# PERfECT-BLE.net
KiCad netlist of a schematic drawn in Altium Designer
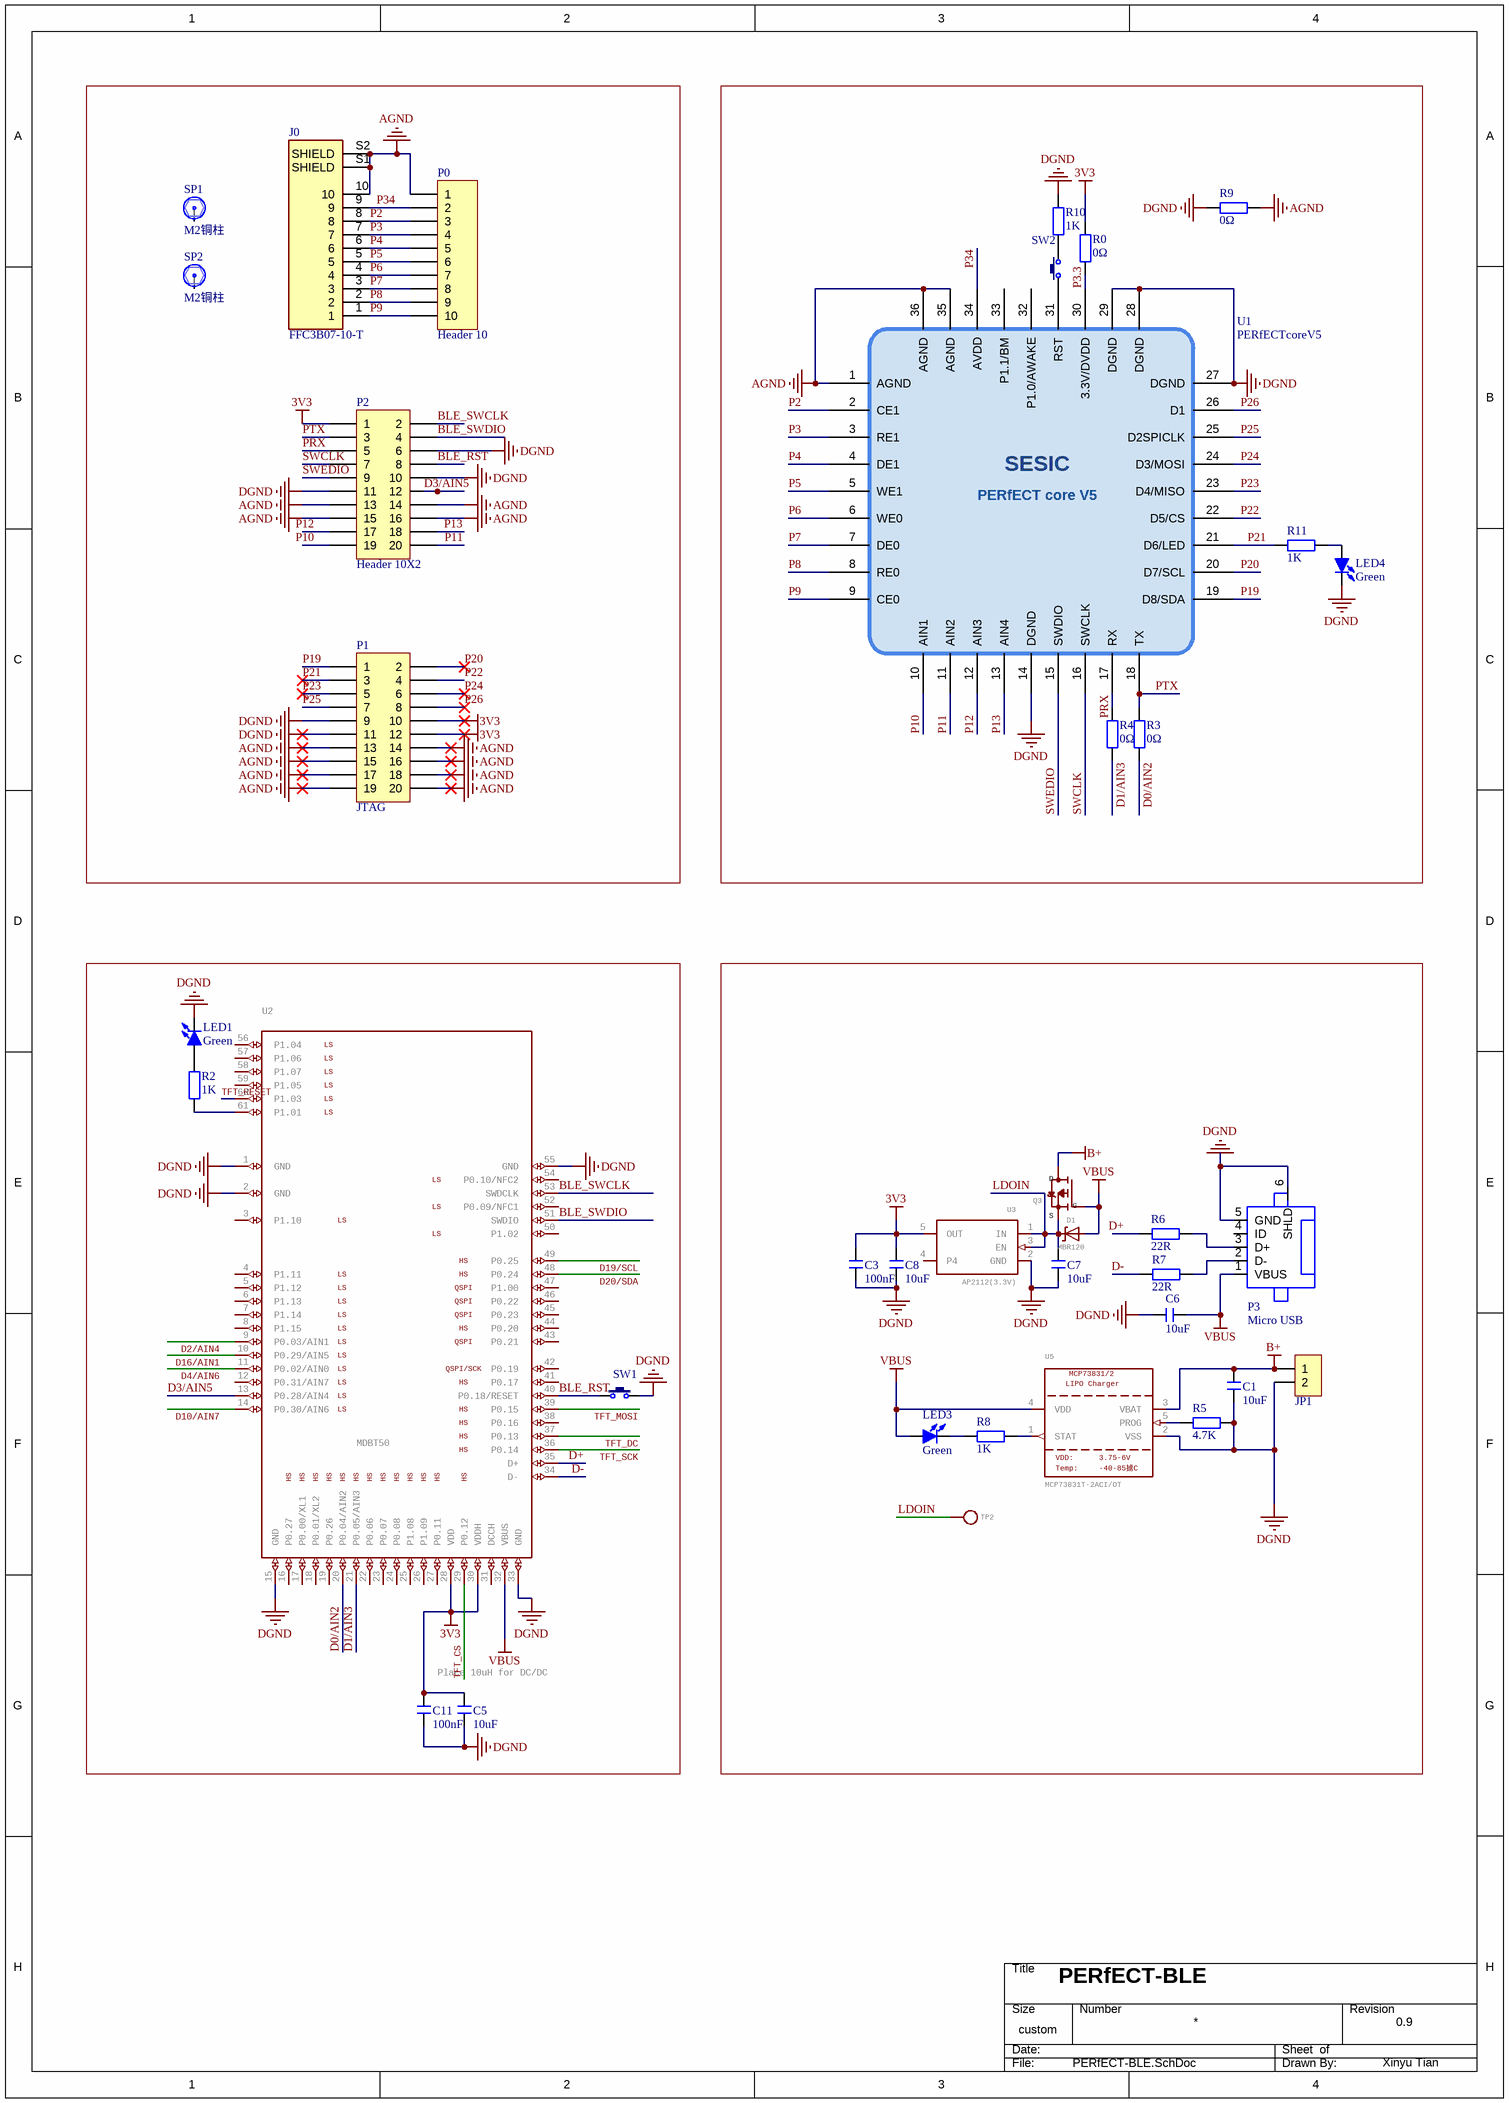
[diagram p0: PERfECT-BLE.SchDoc]

(export (version "E")
  (design (tool "Eeschema 10.0.6"))
  (components
    (comp (ref "C1")
      (value "10uF")
      (footprint "LC-0603_C")
      (description "无极性贴片电容")
      (fields (field (name "版权归属") "源创客"))
      (libsource (lib "3.1   - 电阻-电容-电感") (part "C"))
    )
    (comp (ref "C3")
      (value "100nF")
      (footprint "LC-0603_C")
      (description "无极性贴片电容")
      (fields (field (name "版权归属") "源创客"))
      (libsource (lib "3.1   - 电阻-电容-电感") (part "C"))
    )
    (comp (ref "C5")
      (value "10uF")
      (footprint "LC-0603_C")
      (description "无极性贴片电容")
      (fields (field (name "版权归属") "源创客"))
      (libsource (lib "3.1   - 电阻-电容-电感") (part "C"))
    )
    (comp (ref "C6")
      (value "10uF")
      (footprint "LC-0603_C")
      (description "无极性贴片电容")
      (fields (field (name "版权归属") "源创客"))
      (libsource (lib "3.1   - 电阻-电容-电感") (part "C"))
    )
    (comp (ref "C7")
      (value "10uF")
      (footprint "LC-0603_C")
      (description "无极性贴片电容")
      (fields (field (name "版权归属") "源创客"))
      (libsource (lib "3.1   - 电阻-电容-电感") (part "C"))
    )
    (comp (ref "C8")
      (value "10uF")
      (footprint "LC-0603_C")
      (description "无极性贴片电容")
      (fields (field (name "版权归属") "源创客"))
      (libsource (lib "3.1   - 电阻-电容-电感") (part "C"))
    )
    (comp (ref "C11")
      (value "100nF")
      (footprint "LC-0603_C")
      (description "无极性贴片电容")
      (fields (field (name "版权归属") "源创客"))
      (libsource (lib "3.1   - 电阻-电容-电感") (part "C"))
    )
    (comp (ref "D1")
      (value "MBR120")
      (footprint "LC-SOD-123")
      (libsource (lib "microbuilder") (part "DIODE-SCHOTTKYSOD-123"))
    )
    (comp (ref "J0")
      (value "FFC3B07-10-T")
      (footprint "GCT_FFC3B07-10-T")
      (description "10 Position FFC, FPC Connector Contacts, Bottom 0.039 (1.00mm) Surface Mount, Right Angle")
      (fields (field (name "MF") "Global Connector Technology"))
      (libsource (lib "FFC3B07-10-T") (part "FFC3B07-10-T"))
    )
    (comp (ref "JP1")
      (value "HDR-1X2")
      (footprint "XH2.54-LI-2P")
      (description "2P接插件")
      (fields (field (name "版权归属") "源创客"))
      (libsource (lib "4.5   - 接插件-脚距2.54") (part "Header 2"))
    )
    (comp (ref "LED1")
      (value "Green")
      (footprint "LC-0603_LED_S1")
      (description "贴片LED")
      (fields (field (name "版权归属") "源创客"))
      (libsource (lib "9.1   - LED") (part "LED-SMD"))
    )
    (comp (ref "LED3")
      (value "Green")
      (footprint "0603_LED_S1")
      (description "贴片LED")
      (fields (field (name "版权归属") "源创客"))
      (libsource (lib "9.1   - LED") (part "LED-SMD"))
    )
    (comp (ref "LED4")
      (value "Green")
      (footprint "LC-0603_LED_S1")
      (description "贴片LED")
      (fields (field (name "版权归属") "源创客"))
      (libsource (lib "9.1   - LED") (part "LED-SMD"))
    )
    (comp (ref "P0")
      (value "Header 10")
      (footprint "HDR1X10")
      (description "Header, 10-Pin")
      (fields (field (name "PUBLISHER") "Altium Limited"))
      (libsource (lib "Miscellaneous Connectors") (part "Header 10"))
    )
    (comp (ref "P1")
      (value "JTAG")
      (footprint "HDR2X10")
      (description "Header, 10-Pin, Dual row")
      (fields (field (name "PUBLISHER") "Altium Limited"))
      (libsource (lib "PERfECT-PRO") (part "Header 10X2"))
    )
    (comp (ref "P2")
      (value "Header 10X2")
      (footprint "HDR2X10")
      (description "Header, 10-Pin, Dual row")
      (fields (field (name "PUBLISHER") "Altium Limited"))
      (libsource (lib "PERfECT-PRO") (part "Header 10X2"))
    )
    (comp (ref "P3")
      (value "Micro USB")
      (footprint "1981584-1")
      (description "CONN RCPT MICRO USB TYPE AB")
      (fields (field (name "MANUFACTURER") "REG CON") (field (name "PARTNUMBER") "C21377"))
      (libsource (lib "ESP32D") (part "1981584-1"))
    )
    (comp (ref "Q3")
      (value "DMG2305")
      (footprint "LC-SOT-23-3L")
      (fields (field (name "D") "D") (field (name "S") "S") (field (name "G") "G"))
      (libsource (lib "microbuilder") (part "MOSFET-P"))
    )
    (comp (ref "R0")
      (value "0Ω")
      (footprint "LC-0603_R")
      (description "贴片电阻")
      (fields (field (name "版权归属") "源创客"))
      (libsource (lib "3.1   - 电阻-电容-电感") (part "R"))
    )
    (comp (ref "R2")
      (value "1K")
      (footprint "LC-0603_R")
      (description "贴片电阻")
      (fields (field (name "版权归属") "源创客"))
      (libsource (lib "3.1   - 电阻-电容-电感") (part "R"))
    )
    (comp (ref "R3")
      (value "0Ω")
      (footprint "0603_R")
      (description "贴片电阻")
      (fields (field (name "版权归属") "源创客"))
      (libsource (lib "3.1   - 电阻-电容-电感") (part "R"))
    )
    (comp (ref "R4")
      (value "0Ω")
      (footprint "0603_R")
      (description "贴片电阻")
      (fields (field (name "版权归属") "源创客"))
      (libsource (lib "3.1   - 电阻-电容-电感") (part "R"))
    )
    (comp (ref "R5")
      (value "4.7K")
      (footprint "LC-0603_R")
      (description "贴片电阻")
      (fields (field (name "版权归属") "源创客"))
      (libsource (lib "3.1   - 电阻-电容-电感") (part "R"))
    )
    (comp (ref "R6")
      (value "22R")
      (footprint "LC-0603_R")
      (description "贴片电阻")
      (fields (field (name "版权归属") "源创客"))
      (libsource (lib "3.1   - 电阻-电容-电感") (part "R"))
    )
    (comp (ref "R7")
      (value "22R")
      (footprint "LC-0603_R")
      (description "贴片电阻")
      (fields (field (name "版权归属") "源创客"))
      (libsource (lib "3.1   - 电阻-电容-电感") (part "R"))
    )
    (comp (ref "R8")
      (value "1K")
      (footprint "0603_R")
      (description "贴片电阻")
      (fields (field (name "版权归属") "源创客"))
      (libsource (lib "3.1   - 电阻-电容-电感") (part "R"))
    )
    (comp (ref "R9")
      (value "0Ω")
      (footprint "LC-0603_R")
      (description "贴片电阻")
      (fields (field (name "版权归属") "源创客"))
      (libsource (lib "3.1   - 电阻-电容-电感") (part "R"))
    )
    (comp (ref "R10")
      (value "1K")
      (footprint "LC-0603_R")
      (description "贴片电阻")
      (fields (field (name "版权归属") "源创客"))
      (libsource (lib "3.1   - 电阻-电容-电感") (part "R"))
    )
    (comp (ref "R11")
      (value "1K")
      (footprint "LC-0603_R")
      (description "贴片电阻")
      (fields (field (name "版权归属") "源创客"))
      (libsource (lib "3.1   - 电阻-电容-电感") (part "R"))
    )
    (comp (ref "SP1")
      (value "M2铜柱")
      (footprint "M3x4_L")
      (description "铜柱")
      (fields (field (name "版权归属") "源创客"))
      (libsource (lib "15.1 - 未分类器件") (part "铜柱小焊盘"))
    )
    (comp (ref "SP2")
      (value "M2铜柱")
      (footprint "M3x4_L")
      (description "铜柱")
      (fields (field (name "版权归属") "源创客"))
      (libsource (lib "15.1 - 未分类器件") (part "铜柱小焊盘"))
    )
    (comp (ref "SW1")
      (value "3x6x5")
      (footprint "TSW SMD-3*6*2.5")
      (description "3x6轻触开关")
      (fields (field (name "版权归属") "源创客"))
      (libsource (lib "") (part "TSW 3x6_1"))
    )
    (comp (ref "SW2")
      (value "3x6x5")
      (footprint "TSW SMD-3*6*2.5")
      (description "3x6轻触开关")
      (fields (field (name "版权归属") "源创客"))
      (libsource (lib "5.1   - 按键-开关") (part "TSW 3x6"))
    )
    (comp (ref "TP2")
      (value "TESTPOINTROUND1.5MM")
      (footprint "TESTPOINT_ROUND_1.5MM")
      (libsource (lib "microbuilder") (part "TESTPOINTROUND1.5MM"))
    )
    (comp (ref "U1")
      (value "PERfECTcoreV5")
      (footprint "PERfECTcore36")
      (description "This is the 5th version of PERfEC core.https://github.com/WISE-PERfECT/PERfECT")
      (libsource (lib "PERfECT-PRO") (part "PERfECTcoreV5"))
    )
    (comp (ref "U2")
      (value "MDBT50")
      (footprint "MDBT50")
      (fields
        (field (name "LS") "LS")
        (field (name "LS_1") "LS")
        (field (name "LS_2") "LS")
        (field (name "LS_3") "LS")
        (field (name "LS_4") "LS")
        (field (name "LS_5") "LS")
        (field (name "LS_6") "LS")
        (field (name "LS_7") "LS")
        (field (name "LS_8") "LS")
        (field (name "HS") "HS")
        (field (name "HS_1") "HS")
        (field (name "HS_2") "HS")
        (field (name "HS_3") "HS")
        (field (name "HS_4") "HS")
        (field (name "HS_5") "HS")
        (field (name "HS_6") "HS")
        (field (name "HS_7") "HS")
        (field (name "HS_8") "HS")
        (field (name "QSPI") "QSPI")
        (field (name "QSPI_1") "QSPI")
        (field (name "QSPI_2") "QSPI")
        (field (name "QSPI_3") "QSPI")
        (field (name "QSPI/SCK") "QSPI/SCK")
      )
      (libsource (lib "microbuilder") (part "MDBT50"))
    )
    (comp (ref "U3")
      (value "AP2112(3.3V)")
      (footprint "Probe-Scope v1.0:SOT23-5")
      (libsource (lib "microbuilder") (part "VREG_SOT23-5"))
    )
    (comp (ref "U5")
      (value "MCP73831T-2ACI/OT")
      (footprint "SOT23-5")
      (fields
        (field (name "MCP73831/2") "MCP73831/2")
        (field (name "LIPOCHARGER") "LIPO Charger")
        (field (name "TEMP") "Temp:")
        (field (name "-40-85掳C") "-40-85掳C")
        (field (name "VDD") "VDD:")
        (field (name "3.75-6V") "3.75-6V")
      )
      (libsource (lib "microbuilder") (part "MCP73831/2"))
    )
  )
  (nets
    (net (code "1") (name "/BLE_RST") (class "Default")
      (node (ref "P2") (pin "8") (pinfunction "8_8") (pintype "passive"))
      (node (ref "SW1") (pin "1") (pinfunction "1_1") (pintype "passive"))
      (node (ref "U2") (pin "40") (pinfunction "P0.18/RESET_40") (pintype "bidirectional"))
    )
    (net (code "2") (name "/BLE_SWCLK") (class "Default")
      (node (ref "P2") (pin "2") (pinfunction "2_2") (pintype "passive"))
      (node (ref "U2") (pin "53") (pinfunction "SWDCLK_53") (pintype "bidirectional"))
    )
    (net (code "3") (name "/BLE_SWDIO") (class "Default")
      (node (ref "P2") (pin "4") (pinfunction "4_4") (pintype "passive"))
      (node (ref "U2") (pin "51") (pinfunction "SWDIO_51") (pintype "bidirectional"))
    )
    (net (code "4") (name "/D+") (class "Default")
      (node (ref "R6") (pin "1") (pinfunction "1_1") (pintype "passive"))
      (node (ref "U2") (pin "35") (pinfunction "D+_35") (pintype "bidirectional"))
    )
    (net (code "5") (name "/D-") (class "Default")
      (node (ref "R7") (pin "1") (pinfunction "1_1") (pintype "passive"))
      (node (ref "U2") (pin "34") (pinfunction "D-_34") (pintype "bidirectional"))
    )
    (net (code "6") (name "/D0{slash}AIN2") (class "Default")
      (node (ref "R3") (pin "2") (pinfunction "2_2") (pintype "passive"))
      (node (ref "U2") (pin "20") (pinfunction "P0.04/AIN2_20") (pintype "bidirectional"))
    )
    (net (code "7") (name "/D1{slash}AIN3") (class "Default")
      (node (ref "R4") (pin "2") (pinfunction "2_2") (pintype "passive"))
      (node (ref "U2") (pin "21") (pinfunction "P0.05/AIN3_21") (pintype "bidirectional"))
    )
    (net (code "8") (name "/D2{slash}AIN4") (class "Default")
      (node (ref "U2") (pin "9") (pinfunction "P0.03/AIN1_9") (pintype "bidirectional"))
    )
    (net (code "9") (name "/D3{slash}AIN5") (class "Default")
      (node (ref "P2") (pin "12") (pinfunction "12_12") (pintype "passive"))
      (node (ref "U2") (pin "13") (pinfunction "P0.28/AIN4_13") (pintype "bidirectional"))
    )
    (net (code "10") (name "/D4{slash}AIN6") (class "Default")
      (node (ref "U2") (pin "11") (pinfunction "P0.02/AIN0_11") (pintype "bidirectional"))
    )
    (net (code "11") (name "/D10{slash}AIN7") (class "Default")
      (node (ref "U2") (pin "14") (pinfunction "P0.30/AIN6_14") (pintype "bidirectional"))
    )
    (net (code "12") (name "/D16{slash}AIN1") (class "Default")
      (node (ref "U2") (pin "10") (pinfunction "P0.29/AIN5_10") (pintype "bidirectional"))
    )
    (net (code "13") (name "/D19{slash}SCL") (class "Default")
      (node (ref "U2") (pin "49") (pinfunction "P0.25_49") (pintype "bidirectional"))
    )
    (net (code "14") (name "/D20{slash}SDA") (class "Default")
      (node (ref "U2") (pin "48") (pinfunction "P0.24_48") (pintype "bidirectional"))
    )
    (net (code "15") (name "/LDOIN") (class "Default")
      (node (ref "C7") (pin "2") (pinfunction "2_2") (pintype "passive"))
      (node (ref "D1") (pin "C") (pinfunction "C_C") (pintype "passive"))
      (node (ref "Q3") (pin "2") (pinfunction "S_2") (pintype "passive"))
      (node (ref "TP2") (pin "P$1") (pinfunction "P$1_P$1") (pintype "bidirectional"))
      (node (ref "U3") (pin "1") (pinfunction "IN_1") (pintype "power_in"))
      (node (ref "U3") (pin "3") (pinfunction "EN_3") (pintype "input"))
    )
    (net (code "16") (name "/P2") (class "Default")
      (node (ref "J0") (pin "8") (pinfunction "8_8") (pintype "passive"))
      (node (ref "P0") (pin "3") (pinfunction "3_3") (pintype "passive"))
      (node (ref "U1") (pin "2") (pinfunction "CE1_2") (pintype "passive"))
    )
    (net (code "17") (name "/P3") (class "Default")
      (node (ref "J0") (pin "7") (pinfunction "7_7") (pintype "passive"))
      (node (ref "P0") (pin "4") (pinfunction "4_4") (pintype "passive"))
      (node (ref "U1") (pin "3") (pinfunction "RE1_3") (pintype "passive"))
    )
    (net (code "18") (name "/P3.3") (class "Default")
      (node (ref "R0") (pin "2") (pinfunction "2_2") (pintype "passive"))
      (node (ref "U1") (pin "30") (pinfunction "3.3V/DVDD_30") (pintype "passive"))
    )
    (net (code "19") (name "/P4") (class "Default")
      (node (ref "J0") (pin "6") (pinfunction "6_6") (pintype "passive"))
      (node (ref "P0") (pin "5") (pinfunction "5_5") (pintype "passive"))
      (node (ref "U1") (pin "4") (pinfunction "DE1_4") (pintype "passive"))
    )
    (net (code "20") (name "/P5") (class "Default")
      (node (ref "J0") (pin "5") (pinfunction "5_5") (pintype "passive"))
      (node (ref "P0") (pin "6") (pinfunction "6_6") (pintype "passive"))
      (node (ref "U1") (pin "5") (pinfunction "WE1_5") (pintype "passive"))
    )
    (net (code "21") (name "/P6") (class "Default")
      (node (ref "J0") (pin "4") (pinfunction "4_4") (pintype "passive"))
      (node (ref "P0") (pin "7") (pinfunction "7_7") (pintype "passive"))
      (node (ref "U1") (pin "6") (pinfunction "WE0_6") (pintype "passive"))
    )
    (net (code "22") (name "/P7") (class "Default")
      (node (ref "J0") (pin "3") (pinfunction "3_3") (pintype "passive"))
      (node (ref "P0") (pin "8") (pinfunction "8_8") (pintype "passive"))
      (node (ref "U1") (pin "7") (pinfunction "DE0_7") (pintype "passive"))
    )
    (net (code "23") (name "/P8") (class "Default")
      (node (ref "J0") (pin "2") (pinfunction "2_2") (pintype "passive"))
      (node (ref "P0") (pin "9") (pinfunction "9_9") (pintype "passive"))
      (node (ref "U1") (pin "8") (pinfunction "RE0_8") (pintype "passive"))
    )
    (net (code "24") (name "/P9") (class "Default")
      (node (ref "J0") (pin "1") (pinfunction "1_1") (pintype "passive"))
      (node (ref "P0") (pin "10") (pinfunction "10_10") (pintype "passive"))
      (node (ref "U1") (pin "9") (pinfunction "CE0_9") (pintype "passive"))
    )
    (net (code "25") (name "/P10") (class "Default")
      (node (ref "P2") (pin "19") (pinfunction "19_19") (pintype "passive"))
      (node (ref "U1") (pin "10") (pinfunction "AIN1_10") (pintype "passive"))
    )
    (net (code "26") (name "/P11") (class "Default")
      (node (ref "P2") (pin "20") (pinfunction "20_20") (pintype "passive"))
      (node (ref "U1") (pin "11") (pinfunction "AIN2_11") (pintype "passive"))
    )
    (net (code "27") (name "/P12") (class "Default")
      (node (ref "P2") (pin "17") (pinfunction "17_17") (pintype "passive"))
      (node (ref "U1") (pin "12") (pinfunction "AIN3_12") (pintype "passive"))
    )
    (net (code "28") (name "/P13") (class "Default")
      (node (ref "P2") (pin "18") (pinfunction "18_18") (pintype "passive"))
      (node (ref "U1") (pin "13") (pinfunction "AIN4_13") (pintype "passive"))
    )
    (net (code "29") (name "/P19") (class "Default")
      (node (ref "P1") (pin "1") (pinfunction "1_1") (pintype "passive"))
      (node (ref "U1") (pin "19") (pinfunction "D8/SDA_19") (pintype "passive"))
    )
    (net (code "30") (name "/P20") (class "Default")
      (node (ref "P1") (pin "2") (pinfunction "2_2") (pintype "passive"))
      (node (ref "U1") (pin "20") (pinfunction "D7/SCL_20") (pintype "passive"))
    )
    (net (code "31") (name "/P21") (class "Default")
      (node (ref "P1") (pin "3") (pinfunction "3_3") (pintype "passive"))
      (node (ref "R11") (pin "1") (pinfunction "1_1") (pintype "passive"))
      (node (ref "U1") (pin "21") (pinfunction "D6/LED_21") (pintype "passive"))
    )
    (net (code "32") (name "/P22") (class "Default")
      (node (ref "P1") (pin "4") (pinfunction "4_4") (pintype "passive"))
      (node (ref "U1") (pin "22") (pinfunction "D5/CS_22") (pintype "passive"))
    )
    (net (code "33") (name "/P23") (class "Default")
      (node (ref "P1") (pin "5") (pinfunction "5_5") (pintype "passive"))
      (node (ref "U1") (pin "23") (pinfunction "D4/MISO_23") (pintype "passive"))
    )
    (net (code "34") (name "/P24") (class "Default")
      (node (ref "P1") (pin "6") (pinfunction "6_6") (pintype "passive"))
      (node (ref "U1") (pin "24") (pinfunction "D3/MOSI_24") (pintype "passive"))
    )
    (net (code "35") (name "/P25") (class "Default")
      (node (ref "P1") (pin "7") (pinfunction "7_7") (pintype "passive"))
      (node (ref "U1") (pin "25") (pinfunction "D2SPICLK_25") (pintype "passive"))
    )
    (net (code "36") (name "/P26") (class "Default")
      (node (ref "P1") (pin "8") (pinfunction "8_8") (pintype "passive"))
      (node (ref "U1") (pin "26") (pinfunction "D1_26") (pintype "passive"))
    )
    (net (code "37") (name "/P34") (class "Default")
      (node (ref "J0") (pin "9") (pinfunction "9_9") (pintype "passive"))
      (node (ref "P0") (pin "2") (pinfunction "2_2") (pintype "passive"))
      (node (ref "U1") (pin "34") (pinfunction "AVDD_34") (pintype "passive"))
    )
    (net (code "38") (name "/PRX") (class "Default")
      (node (ref "P2") (pin "5") (pinfunction "5_5") (pintype "passive"))
      (node (ref "R4") (pin "1") (pinfunction "1_1") (pintype "passive"))
      (node (ref "U1") (pin "17") (pinfunction "RX_17") (pintype "passive"))
    )
    (net (code "39") (name "/PTX") (class "Default")
      (node (ref "P2") (pin "3") (pinfunction "3_3") (pintype "passive"))
      (node (ref "R3") (pin "1") (pinfunction "1_1") (pintype "passive"))
      (node (ref "U1") (pin "18") (pinfunction "TX_18") (pintype "passive"))
    )
    (net (code "40") (name "/SWCLK") (class "Default")
      (node (ref "P2") (pin "7") (pinfunction "7_7") (pintype "passive"))
      (node (ref "U1") (pin "16") (pinfunction "SWCLK_16") (pintype "passive"))
    )
    (net (code "41") (name "/SWEDIO") (class "Default")
      (node (ref "P2") (pin "9") (pinfunction "9_9") (pintype "passive"))
      (node (ref "U1") (pin "15") (pinfunction "SWDIO_15") (pintype "passive"))
    )
    (net (code "42") (name "/TFT_CS") (class "Default")
      (node (ref "U2") (pin "29") (pinfunction "P0.12_29") (pintype "bidirectional"))
    )
    (net (code "43") (name "/TFT_DC") (class "Default")
      (node (ref "U2") (pin "37") (pinfunction "P0.13_37") (pintype "bidirectional"))
    )
    (net (code "44") (name "/TFT_MOSI") (class "Default")
      (node (ref "U2") (pin "39") (pinfunction "P0.15_39") (pintype "bidirectional"))
    )
    (net (code "45") (name "/TFT_RESET") (class "Default")
      (node (ref "U2") (pin "60") (pinfunction "P1.03_60") (pintype "bidirectional"))
    )
    (net (code "46") (name "/TFT_SCK") (class "Default")
      (node (ref "U2") (pin "36") (pinfunction "P0.14_36") (pintype "bidirectional"))
    )
    (net (code "47") (name "3V3") (class "Default")
      (node (ref "C11") (pin "2") (pinfunction "2_2") (pintype "passive"))
      (node (ref "C3") (pin "2") (pinfunction "2_2") (pintype "passive"))
      (node (ref "C5") (pin "2") (pinfunction "2_2") (pintype "passive"))
      (node (ref "C8") (pin "2") (pinfunction "2_2") (pintype "passive"))
      (node (ref "P1") (pin "10") (pinfunction "10_10") (pintype "passive"))
      (node (ref "P1") (pin "12") (pinfunction "12_12") (pintype "passive"))
      (node (ref "P2") (pin "1") (pinfunction "1_1") (pintype "passive"))
      (node (ref "R0") (pin "1") (pinfunction "1_1") (pintype "passive"))
      (node (ref "U2") (pin "28") (pinfunction "VDD_28") (pintype "bidirectional"))
      (node (ref "U2") (pin "30") (pinfunction "VDDH_30") (pintype "bidirectional"))
      (node (ref "U3") (pin "5") (pinfunction "OUT_5") (pintype "power_in"))
    )
    (net (code "48") (name "AGND") (class "Default")
      (node (ref "J0") (pin "10") (pinfunction "10_10") (pintype "passive"))
      (node (ref "J0") (pin "S1") (pinfunction "SHIELD_S1") (pintype "passive"))
      (node (ref "J0") (pin "S2") (pinfunction "SHIELD_S2") (pintype "passive"))
      (node (ref "P0") (pin "1") (pinfunction "1_1") (pintype "passive"))
      (node (ref "P1") (pin "13") (pinfunction "13_13") (pintype "passive"))
      (node (ref "P1") (pin "14") (pinfunction "14_14") (pintype "passive"))
      (node (ref "P1") (pin "15") (pinfunction "15_15") (pintype "passive"))
      (node (ref "P1") (pin "16") (pinfunction "16_16") (pintype "passive"))
      (node (ref "P1") (pin "17") (pinfunction "17_17") (pintype "passive"))
      (node (ref "P1") (pin "18") (pinfunction "18_18") (pintype "passive"))
      (node (ref "P1") (pin "19") (pinfunction "19_19") (pintype "passive"))
      (node (ref "P1") (pin "20") (pinfunction "20_20") (pintype "passive"))
      (node (ref "P2") (pin "13") (pinfunction "13_13") (pintype "passive"))
      (node (ref "P2") (pin "14") (pinfunction "14_14") (pintype "passive"))
      (node (ref "P2") (pin "15") (pinfunction "15_15") (pintype "passive"))
      (node (ref "P2") (pin "16") (pinfunction "16_16") (pintype "passive"))
      (node (ref "R9") (pin "2") (pinfunction "2_2") (pintype "passive"))
      (node (ref "U1") (pin "1") (pinfunction "AGND_1") (pintype "passive"))
      (node (ref "U1") (pin "35") (pinfunction "AGND_35") (pintype "passive"))
      (node (ref "U1") (pin "36") (pinfunction "AGND_36") (pintype "passive"))
    )
    (net (code "49") (name "B+") (class "Default")
      (node (ref "C1") (pin "2") (pinfunction "2_2") (pintype "passive"))
      (node (ref "JP1") (pin "1") (pinfunction "1_1") (pintype "passive"))
      (node (ref "Q3") (pin "3") (pinfunction "D_3") (pintype "passive"))
      (node (ref "U5") (pin "3") (pinfunction "VBAT_3") (pintype "power_in"))
    )
    (net (code "50") (name "DGND") (class "Default")
      (node (ref "C1") (pin "1") (pinfunction "1_1") (pintype "passive"))
      (node (ref "C11") (pin "1") (pinfunction "1_1") (pintype "passive"))
      (node (ref "C3") (pin "1") (pinfunction "1_1") (pintype "passive"))
      (node (ref "C5") (pin "1") (pinfunction "1_1") (pintype "passive"))
      (node (ref "C6") (pin "2") (pinfunction "2_2") (pintype "passive"))
      (node (ref "C7") (pin "1") (pinfunction "1_1") (pintype "passive"))
      (node (ref "C8") (pin "1") (pinfunction "1_1") (pintype "passive"))
      (node (ref "JP1") (pin "2") (pinfunction "2_2") (pintype "passive"))
      (node (ref "LED1") (pin "2") (pinfunction "K_2") (pintype "passive"))
      (node (ref "LED4") (pin "2") (pinfunction "K_2") (pintype "passive"))
      (node (ref "P1") (pin "11") (pinfunction "11_11") (pintype "passive"))
      (node (ref "P1") (pin "9") (pinfunction "9_9") (pintype "passive"))
      (node (ref "P2") (pin "10") (pinfunction "10_10") (pintype "passive"))
      (node (ref "P2") (pin "11") (pinfunction "11_11") (pintype "passive"))
      (node (ref "P2") (pin "6") (pinfunction "6_6") (pintype "passive"))
      (node (ref "P3") (pin "5") (pinfunction "GND_5") (pintype "power_in"))
      (node (ref "P3") (pin "6") (pinfunction "SHLD_6") (pintype "power_in"))
      (node (ref "R10") (pin "2") (pinfunction "2_2") (pintype "passive"))
      (node (ref "R5") (pin "2") (pinfunction "2_2") (pintype "passive"))
      (node (ref "R9") (pin "1") (pinfunction "1_1") (pintype "passive"))
      (node (ref "SW1") (pin "2") (pinfunction "2_2") (pintype "passive"))
      (node (ref "U1") (pin "14") (pinfunction "DGND_14") (pintype "passive"))
      (node (ref "U1") (pin "27") (pinfunction "DGND_27") (pintype "passive"))
      (node (ref "U1") (pin "28") (pinfunction "DGND_28") (pintype "power_in"))
      (node (ref "U1") (pin "29") (pinfunction "DGND_29") (pintype "passive"))
      (node (ref "U2") (pin "1") (pinfunction "GND_1") (pintype "bidirectional"))
      (node (ref "U2") (pin "15") (pinfunction "GND_15") (pintype "bidirectional"))
      (node (ref "U2") (pin "2") (pinfunction "GND_2") (pintype "bidirectional"))
      (node (ref "U2") (pin "33") (pinfunction "GND_33") (pintype "bidirectional"))
      (node (ref "U2") (pin "55") (pinfunction "GND_55") (pintype "bidirectional"))
      (node (ref "U3") (pin "2") (pinfunction "GND_2") (pintype "power_in"))
      (node (ref "U5") (pin "2") (pinfunction "VSS_2") (pintype "power_in"))
    )
    (net (code "51") (name "Net-(LED1-A)") (class "Default")
      (node (ref "LED1") (pin "1") (pinfunction "A_1") (pintype "passive"))
      (node (ref "R2") (pin "2") (pinfunction "2_2") (pintype "passive"))
    )
    (net (code "52") (name "Net-(LED3-K)") (class "Default")
      (node (ref "LED3") (pin "2") (pinfunction "K_2") (pintype "passive"))
      (node (ref "R8") (pin "1") (pinfunction "1_1") (pintype "passive"))
    )
    (net (code "53") (name "Net-(LED4-A)") (class "Default")
      (node (ref "LED4") (pin "1") (pinfunction "A_1") (pintype "passive"))
      (node (ref "R11") (pin "2") (pinfunction "2_2") (pintype "passive"))
    )
    (net (code "54") (name "Net-(P3-D+)") (class "Default")
      (node (ref "P3") (pin "3") (pinfunction "D+_3") (pintype "passive"))
      (node (ref "R6") (pin "2") (pinfunction "2_2") (pintype "passive"))
    )
    (net (code "55") (name "Net-(P3-D-)") (class "Default")
      (node (ref "P3") (pin "2") (pinfunction "D-_2") (pintype "passive"))
      (node (ref "R7") (pin "2") (pinfunction "2_2") (pintype "passive"))
    )
    (net (code "56") (name "Net-(R10-Pad1)") (class "Default")
      (node (ref "R10") (pin "1") (pinfunction "1_1") (pintype "passive"))
      (node (ref "SW2") (pin "2") (pinfunction "2_2") (pintype "passive"))
    )
    (net (code "57") (name "Net-(U1-RST)") (class "Default")
      (node (ref "SW2") (pin "1") (pinfunction "1_1") (pintype "passive"))
      (node (ref "U1") (pin "31") (pinfunction "RST_31") (pintype "passive"))
    )
    (net (code "58") (name "Net-(U2-P1.01)") (class "Default")
      (node (ref "R2") (pin "1") (pinfunction "1_1") (pintype "passive"))
      (node (ref "U2") (pin "61") (pinfunction "P1.01_61") (pintype "bidirectional"))
    )
    (net (code "59") (name "Net-(U5-PROG)") (class "Default")
      (node (ref "R5") (pin "1") (pinfunction "1_1") (pintype "passive"))
      (node (ref "U5") (pin "5") (pinfunction "PROG_5") (pintype "input"))
    )
    (net (code "60") (name "Net-(U5-STAT)") (class "Default")
      (node (ref "R8") (pin "2") (pinfunction "2_2") (pintype "passive"))
      (node (ref "U5") (pin "1") (pinfunction "STAT_1") (pintype "output"))
    )
    (net (code "61") (name "VBUS") (class "Default")
      (node (ref "C6") (pin "1") (pinfunction "1_1") (pintype "passive"))
      (node (ref "D1") (pin "A") (pinfunction "A_A") (pintype "passive"))
      (node (ref "LED3") (pin "1") (pinfunction "A_1") (pintype "passive"))
      (node (ref "P3") (pin "1") (pinfunction "VBUS_1") (pintype "power_in"))
      (node (ref "Q3") (pin "1") (pinfunction "G_1") (pintype "passive"))
      (node (ref "U2") (pin "32") (pinfunction "VBUS_32") (pintype "bidirectional"))
      (node (ref "U5") (pin "4") (pinfunction "VDD_4") (pintype "power_in"))
    )
    (net (code "62") (name "unconnected-(P3-ID-Pad4)") (class "Default")
      (node (ref "P3") (pin "4") (pinfunction "ID_4") (pintype "passive"))
    )
    (net (code "63") (name "unconnected-(SP1-Pad1)") (class "Default")
      (node (ref "SP1") (pin "1") (pinfunction "1_1") (pintype "passive"))
    )
    (net (code "64") (name "unconnected-(SP2-Pad1)") (class "Default")
      (node (ref "SP2") (pin "1") (pinfunction "1_1") (pintype "passive"))
    )
    (net (code "65") (name "unconnected-(U1-P1.0{slash}AWAKE-Pad32)") (class "Default")
      (node (ref "U1") (pin "32") (pinfunction "P1.0/AWAKE_32") (pintype "passive"))
    )
    (net (code "66") (name "unconnected-(U1-P1.1{slash}BM-Pad33)") (class "Default")
      (node (ref "U1") (pin "33") (pinfunction "P1.1/BM_33") (pintype "passive"))
    )
    (net (code "67") (name "unconnected-(U2-DCCH-Pad31)") (class "Default")
      (node (ref "U2") (pin "31") (pinfunction "DCCH_31") (pintype "bidirectional"))
    )
    (net (code "68") (name "unconnected-(U2-P0.00{slash}XL1-Pad17)") (class "Default")
      (node (ref "U2") (pin "17") (pinfunction "P0.00/XL1_17") (pintype "bidirectional"))
    )
    (net (code "69") (name "unconnected-(U2-P0.01{slash}XL2-Pad18)") (class "Default")
      (node (ref "U2") (pin "18") (pinfunction "P0.01/XL2_18") (pintype "bidirectional"))
    )
    (net (code "70") (name "unconnected-(U2-P0.06-Pad22)") (class "Default")
      (node (ref "U2") (pin "22") (pinfunction "P0.06_22") (pintype "bidirectional"))
    )
    (net (code "71") (name "unconnected-(U2-P0.07-Pad23)") (class "Default")
      (node (ref "U2") (pin "23") (pinfunction "P0.07_23") (pintype "bidirectional"))
    )
    (net (code "72") (name "unconnected-(U2-P0.08-Pad24)") (class "Default")
      (node (ref "U2") (pin "24") (pinfunction "P0.08_24") (pintype "bidirectional"))
    )
    (net (code "73") (name "unconnected-(U2-P0.09{slash}NFC1-Pad52)") (class "Default")
      (node (ref "U2") (pin "52") (pinfunction "P0.09/NFC1_52") (pintype "bidirectional"))
    )
    (net (code "74") (name "unconnected-(U2-P0.10{slash}NFC2-Pad54)") (class "Default")
      (node (ref "U2") (pin "54") (pinfunction "P0.10/NFC2_54") (pintype "bidirectional"))
    )
    (net (code "75") (name "unconnected-(U2-P0.11-Pad27)") (class "Default")
      (node (ref "U2") (pin "27") (pinfunction "P0.11_27") (pintype "bidirectional"))
    )
    (net (code "76") (name "unconnected-(U2-P0.16-Pad38)") (class "Default")
      (node (ref "U2") (pin "38") (pinfunction "P0.16_38") (pintype "bidirectional"))
    )
    (net (code "77") (name "unconnected-(U2-P0.17-Pad41)") (class "Default")
      (node (ref "U2") (pin "41") (pinfunction "P0.17_41") (pintype "bidirectional"))
    )
    (net (code "78") (name "unconnected-(U2-P0.19-Pad42)") (class "Default")
      (node (ref "U2") (pin "42") (pinfunction "P0.19_42") (pintype "bidirectional"))
    )
    (net (code "79") (name "unconnected-(U2-P0.20-Pad44)") (class "Default")
      (node (ref "U2") (pin "44") (pinfunction "P0.20_44") (pintype "bidirectional"))
    )
    (net (code "80") (name "unconnected-(U2-P0.21-Pad43)") (class "Default")
      (node (ref "U2") (pin "43") (pinfunction "P0.21_43") (pintype "bidirectional"))
    )
    (net (code "81") (name "unconnected-(U2-P0.22-Pad46)") (class "Default")
      (node (ref "U2") (pin "46") (pinfunction "P0.22_46") (pintype "bidirectional"))
    )
    (net (code "82") (name "unconnected-(U2-P0.23-Pad45)") (class "Default")
      (node (ref "U2") (pin "45") (pinfunction "P0.23_45") (pintype "bidirectional"))
    )
    (net (code "83") (name "unconnected-(U2-P0.26-Pad19)") (class "Default")
      (node (ref "U2") (pin "19") (pinfunction "P0.26_19") (pintype "bidirectional"))
    )
    (net (code "84") (name "unconnected-(U2-P0.27-Pad16)") (class "Default")
      (node (ref "U2") (pin "16") (pinfunction "P0.27_16") (pintype "bidirectional"))
    )
    (net (code "85") (name "unconnected-(U2-P0.31{slash}AIN7-Pad12)") (class "Default")
      (node (ref "U2") (pin "12") (pinfunction "P0.31/AIN7_12") (pintype "bidirectional"))
    )
    (net (code "86") (name "unconnected-(U2-P1.00-Pad47)") (class "Default")
      (node (ref "U2") (pin "47") (pinfunction "P1.00_47") (pintype "bidirectional"))
    )
    (net (code "87") (name "unconnected-(U2-P1.02-Pad50)") (class "Default")
      (node (ref "U2") (pin "50") (pinfunction "P1.02_50") (pintype "bidirectional"))
    )
    (net (code "88") (name "unconnected-(U2-P1.04-Pad56)") (class "Default")
      (node (ref "U2") (pin "56") (pinfunction "P1.04_56") (pintype "bidirectional"))
    )
    (net (code "89") (name "unconnected-(U2-P1.05-Pad59)") (class "Default")
      (node (ref "U2") (pin "59") (pinfunction "P1.05_59") (pintype "bidirectional"))
    )
    (net (code "90") (name "unconnected-(U2-P1.06-Pad57)") (class "Default")
      (node (ref "U2") (pin "57") (pinfunction "P1.06_57") (pintype "bidirectional"))
    )
    (net (code "91") (name "unconnected-(U2-P1.07-Pad58)") (class "Default")
      (node (ref "U2") (pin "58") (pinfunction "P1.07_58") (pintype "bidirectional"))
    )
    (net (code "92") (name "unconnected-(U2-P1.08-Pad25)") (class "Default")
      (node (ref "U2") (pin "25") (pinfunction "P1.08_25") (pintype "bidirectional"))
    )
    (net (code "93") (name "unconnected-(U2-P1.09-Pad26)") (class "Default")
      (node (ref "U2") (pin "26") (pinfunction "P1.09_26") (pintype "bidirectional"))
    )
    (net (code "94") (name "unconnected-(U2-P1.10-Pad3)") (class "Default")
      (node (ref "U2") (pin "3") (pinfunction "P1.10_3") (pintype "bidirectional"))
    )
    (net (code "95") (name "unconnected-(U2-P1.11-Pad4)") (class "Default")
      (node (ref "U2") (pin "4") (pinfunction "P1.11_4") (pintype "bidirectional"))
    )
    (net (code "96") (name "unconnected-(U2-P1.12-Pad5)") (class "Default")
      (node (ref "U2") (pin "5") (pinfunction "P1.12_5") (pintype "bidirectional"))
    )
    (net (code "97") (name "unconnected-(U2-P1.13-Pad6)") (class "Default")
      (node (ref "U2") (pin "6") (pinfunction "P1.13_6") (pintype "bidirectional"))
    )
    (net (code "98") (name "unconnected-(U2-P1.14-Pad7)") (class "Default")
      (node (ref "U2") (pin "7") (pinfunction "P1.14_7") (pintype "bidirectional"))
    )
    (net (code "99") (name "unconnected-(U2-P1.15-Pad8)") (class "Default")
      (node (ref "U2") (pin "8") (pinfunction "P1.15_8") (pintype "bidirectional"))
    )
    (net (code "100") (name "unconnected-(U3-P4-Pad4)") (class "Default")
      (node (ref "U3") (pin "4") (pinfunction "P4_4") (pintype "bidirectional"))
    )
  )
)
